# OpenTenkiEasyEda.net
KiCad netlist of a schematic drawn in EasyEDA Pro
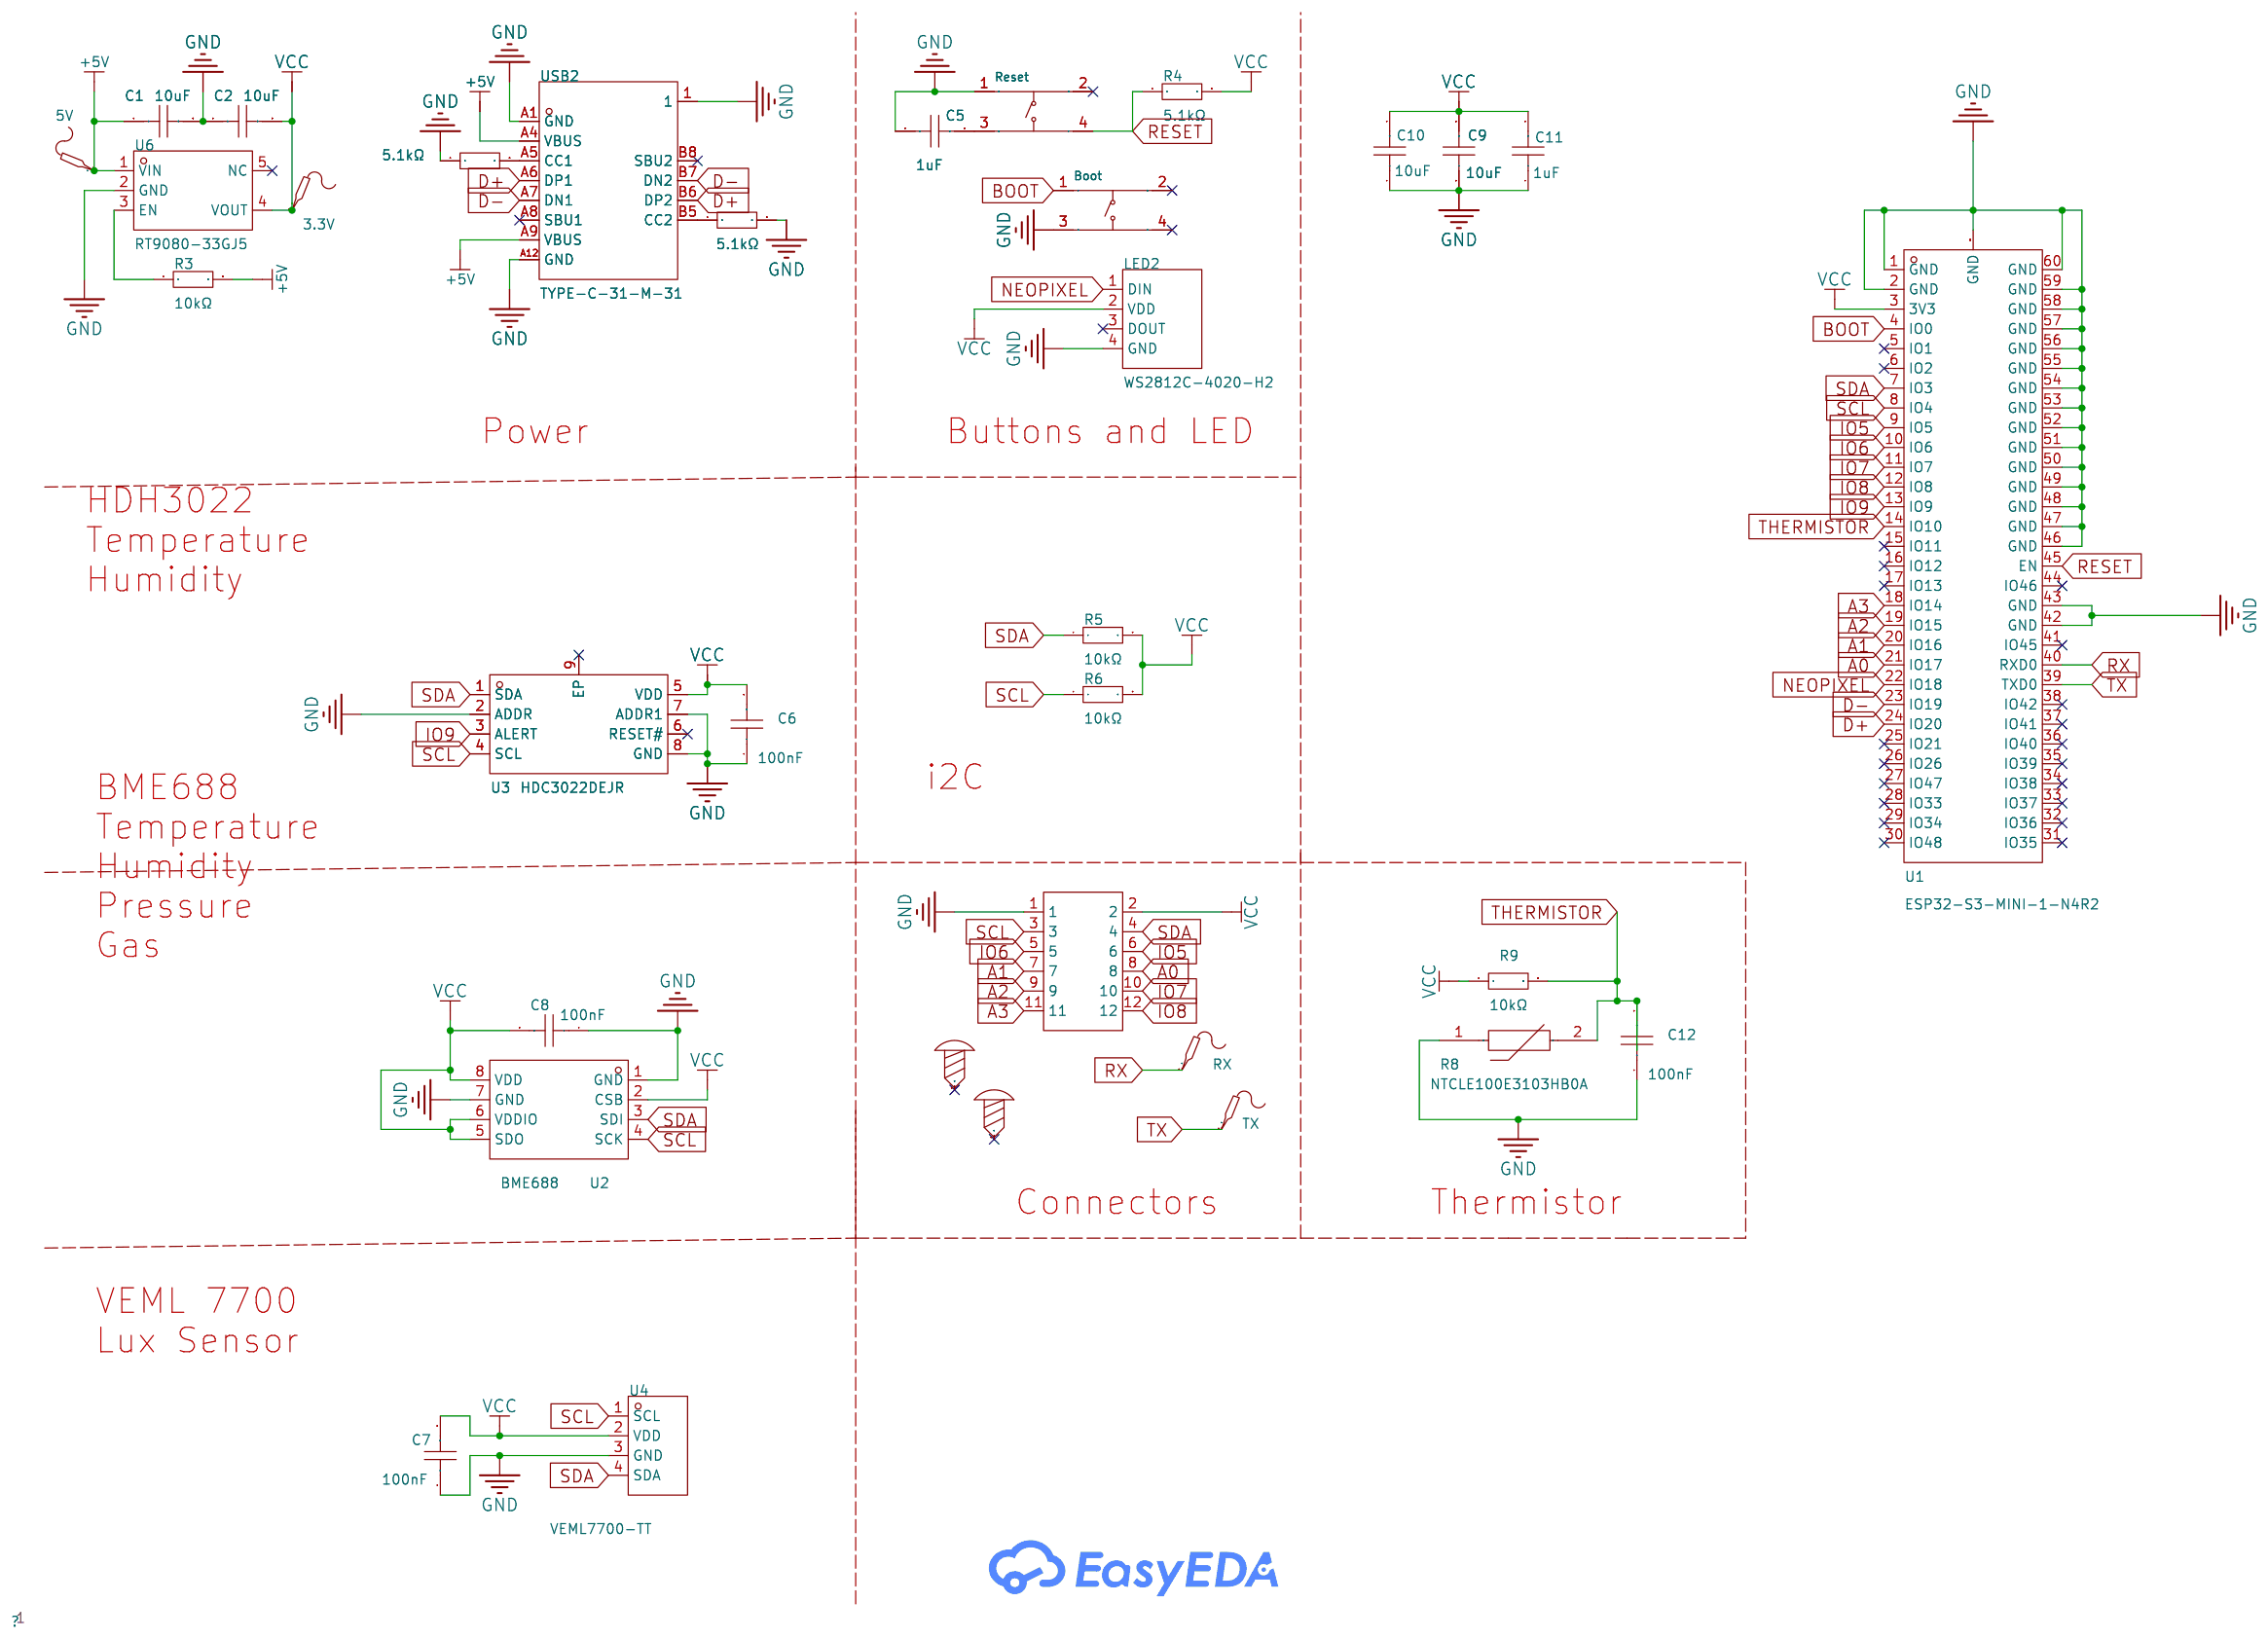
[diagram p0: schematic sheet]

(export (version "E")
  (design (tool "Eeschema 10.0.6"))
  (components
    (comp (ref "3.3V")
      (value "~")
      (footprint "easyedapro:Test-Point-0.5mm")
      (description "Test Point 测试点")
      (libsource (lib "easyedapro") (part "Test-Point"))
    )
    (comp (ref "5V")
      (value "~")
      (footprint "easyedapro:Test-Point-0.5mm")
      (description "Test Point 测试点")
      (libsource (lib "easyedapro") (part "Test-Point"))
    )
    (comp (ref "Boot")
      (value "TSD4A 250gf-DZ")
      (footprint "easyedapro:SW-SMD_TSD4A")
      (fields (field (name "Manufacturer") "SHOU HAN(首韩)"))
      (libsource (lib "easyedapro") (part "TSD4A 250GF-DZ"))
    )
    (comp (ref "C1")
      (value "10uF")
      (footprint "easyedapro:C0603")
      (fields
        (field (name "Manufacturer Part") "CL10A106KP8NNNC")
        (field (name "Manufacturer") "SAMSUNG(三星)")
      )
      (libsource (lib "easyedapro") (part "CL10A106KP8NNNC"))
    )
    (comp (ref "C2")
      (value "10uF")
      (footprint "easyedapro:C0603")
      (fields
        (field (name "Manufacturer Part") "CL10A106KP8NNNC")
        (field (name "Manufacturer") "SAMSUNG(三星)")
      )
      (libsource (lib "easyedapro") (part "CL10A106KP8NNNC"))
    )
    (comp (ref "C5")
      (value "1uF")
      (footprint "easyedapro:C0603")
      (fields
        (field (name "Manufacturer Part") "CL10A105KB8NNNC")
        (field (name "Manufacturer") "SAMSUNG(三星)")
      )
      (libsource (lib "easyedapro") (part "CL10A105KB8NNNC"))
    )
    (comp (ref "C6")
      (value "100nF")
      (footprint "easyedapro:C0603")
      (description "Capacitance:100nF Tolerance:±10% Tolerance:±10% Voltage Rating:50V Temperature Coefficient:X7R")
      (fields
        (field (name "Manufacturer Part") "CC0603KRX7R9BB104")
        (field (name "Manufacturer") "YAGEO(国巨)")
      )
      (libsource (lib "easyedapro") (part "CC0603KRX7R9BB104"))
    )
    (comp (ref "C7")
      (value "100nF")
      (footprint "easyedapro:C0603")
      (description "Capacitance:100nF Tolerance:±10% Tolerance:±10% Voltage Rating:50V Temperature Coefficient:X7R")
      (fields
        (field (name "Manufacturer Part") "CC0603KRX7R9BB104")
        (field (name "Manufacturer") "YAGEO(国巨)")
      )
      (libsource (lib "easyedapro") (part "CC0603KRX7R9BB104"))
    )
    (comp (ref "C8")
      (value "100nF")
      (footprint "easyedapro:C0603")
      (description "Capacitance:100nF Tolerance:±10% Tolerance:±10% Voltage Rating:50V Temperature Coefficient:X7R")
      (fields
        (field (name "Manufacturer Part") "CC0603KRX7R9BB104")
        (field (name "Manufacturer") "YAGEO(国巨)")
      )
      (libsource (lib "easyedapro") (part "CC0603KRX7R9BB104"))
    )
    (comp (ref "C9")
      (value "10uF")
      (footprint "easyedapro:C0603")
      (fields
        (field (name "Manufacturer Part") "CL10A106KP8NNNC")
        (field (name "Manufacturer") "SAMSUNG(三星)")
      )
      (libsource (lib "easyedapro") (part "CL10A106KP8NNNC"))
    )
    (comp (ref "C10")
      (value "10uF")
      (footprint "easyedapro:C0603")
      (fields
        (field (name "Manufacturer Part") "CL10A106KP8NNNC")
        (field (name "Manufacturer") "SAMSUNG(三星)")
      )
      (libsource (lib "easyedapro") (part "CL10A106KP8NNNC"))
    )
    (comp (ref "C11")
      (value "1uF")
      (footprint "easyedapro:C0603")
      (fields
        (field (name "Manufacturer Part") "CL10A105KB8NNNC")
        (field (name "Manufacturer") "SAMSUNG(三星)")
      )
      (libsource (lib "easyedapro") (part "CL10A105KB8NNNC"))
    )
    (comp (ref "C12")
      (value "100nF")
      (footprint "easyedapro:C0603")
      (description "Capacitance:100nF Tolerance:±10% Tolerance:±10% Voltage Rating:50V Temperature Coefficient:X7R")
      (fields
        (field (name "Manufacturer Part") "CC0603KRX7R9BB104")
        (field (name "Manufacturer") "YAGEO(国巨)")
      )
      (libsource (lib "easyedapro") (part "CC0603KRX7R9BB104"))
    )
    (comp (ref "LED2")
      (value "WS2812C-4020-H2")
      (footprint "easyedapro:LED-SMD_4P-L4.0-W1.7_DCS-CA4020A0R02G02B02CE004")
      (fields (field (name "Manufacturer") "worldsemi"))
      (libsource (lib "easyedapro") (part "WS2812C-4020-H2"))
    )
    (comp (ref "R3")
      (value "10kΩ")
      (footprint "easyedapro:R0603")
      (fields (field (name "Manufacturer Part") "RC0603FR-0710KL") (field (name "Manufacturer") "YAGEO(国巨)"))
      (libsource (lib "easyedapro") (part "RC0603FR-0710KL"))
    )
    (comp (ref "R4")
      (value "5.1kΩ")
      (footprint "easyedapro:R0603")
      (fields (field (name "Manufacturer Part") "RC0603FR-075K1L") (field (name "Manufacturer") "YAGEO(国巨)"))
      (libsource (lib "easyedapro") (part "RC0603FR-075K1L"))
    )
    (comp (ref "R5")
      (value "10kΩ")
      (footprint "easyedapro:R0603")
      (fields (field (name "Manufacturer Part") "RC0603FR-0710KL") (field (name "Manufacturer") "YAGEO(国巨)"))
      (libsource (lib "easyedapro") (part "RC0603FR-0710KL"))
    )
    (comp (ref "R6")
      (value "10kΩ")
      (footprint "easyedapro:R0603")
      (fields (field (name "Manufacturer Part") "RC0603FR-0710KL") (field (name "Manufacturer") "YAGEO(国巨)"))
      (libsource (lib "easyedapro") (part "RC0603FR-0710KL"))
    )
    (comp (ref "R8")
      (value "NTCLE100E3103HB0A")
      (footprint "easyedapro:RES-TH_L6.0-W3.0-P2.54-D0.6")
      (fields (field (name "Manufacturer") "VISHAY(威世)"))
      (libsource (lib "easyedapro") (part "NTCLE100E3103HT1"))
    )
    (comp (ref "R9")
      (value "10kΩ")
      (footprint "easyedapro:R0603")
      (fields (field (name "Manufacturer Part") "RC0603FR-0710KL") (field (name "Manufacturer") "YAGEO(国巨)"))
      (libsource (lib "easyedapro") (part "RC0603FR-0710KL"))
    )
    (comp (ref "R10")
      (value "5.1kΩ")
      (footprint "easyedapro:R0603")
      (fields (field (name "Manufacturer Part") "RC0603FR-075K1L") (field (name "Manufacturer") "YAGEO(国巨)"))
      (libsource (lib "easyedapro") (part "RC0603FR-075K1L"))
    )
    (comp (ref "R11")
      (value "5.1kΩ")
      (footprint "easyedapro:R0603")
      (fields (field (name "Manufacturer Part") "RC0603FR-075K1L") (field (name "Manufacturer") "YAGEO(国巨)"))
      (libsource (lib "easyedapro") (part "RC0603FR-075K1L"))
    )
    (comp (ref "Reset")
      (value "TSD4A 250gf-DZ")
      (footprint "easyedapro:SW-SMD_TSD4A")
      (fields (field (name "Manufacturer") "SHOU HAN(首韩)"))
      (libsource (lib "easyedapro") (part "TSD4A 250GF-DZ"))
    )
    (comp (ref "RX")
      (value "~")
      (footprint "easyedapro:Test-Point-0.5mm")
      (description "Test Point 测试点")
      (libsource (lib "easyedapro") (part "Test-Point"))
    )
    (comp (ref "SCREW2")
      (value "~")
      (footprint "easyedapro:Screw-Hole-M2")
      (libsource (lib "easyedapro") (part "Screw-Hole"))
    )
    (comp (ref "SCREW4")
      (value "~")
      (footprint "easyedapro:Screw-Hole-M2")
      (libsource (lib "easyedapro") (part "Screw-Hole"))
    )
    (comp (ref "TX")
      (value "~")
      (footprint "easyedapro:Test-Point-0.5mm")
      (description "Test Point 测试点")
      (libsource (lib "easyedapro") (part "Test-Point"))
    )
    (comp (ref "U1")
      (value "ESP32-S3-MINI-1-N4R2")
      (footprint "easyedapro:BULETM-SMD_ESP32-S3-MINI-1-N8")
      (description "Antenna Type:On-Board PCB Antenna")
      (fields (field (name "Manufacturer") "ESPRESSIF(乐鑫)"))
      (libsource (lib "easyedapro") (part "ESP32-S3-MINI-1-N4R2"))
    )
    (comp (ref "U2")
      (value "BME688")
      (footprint "easyedapro:LGA-8_L3.0-W3.0-P0.80_BME688")
      (fields (field (name "Manufacturer") "Bosch(博世)"))
      (libsource (lib "easyedapro") (part "BME688_C3664478"))
    )
    (comp (ref "U3")
      (value "HDC3022DEJR")
      (footprint "easyedapro:TDFN-8_L2.5-W2.5-P0.50-BL-EP")
      (description "Supply Voltage:1.62V~5.5V Supply Voltage:1.62V~5.5V")
      (fields (field (name "Manufacturer") "TI(德州仪器)"))
      (libsource (lib "easyedapro") (part "HDC3022DEJR"))
    )
    (comp (ref "U4")
      (value "VEML7700-TT")
      (footprint "easyedapro:SENSOR-SMD_EML7700-TT")
      (fields (field (name "Manufacturer") "VISHAY(威世)"))
      (libsource (lib "easyedapro") (part "VEML7700-TT"))
    )
    (comp (ref "U6")
      (value "RT9080-33GJ5")
      (footprint "easyedapro:SOT-23-5_L3.0-W1.5-P0.95-LS2.8-BL")
      (fields (field (name "Manufacturer") "TECH PUBLIC(台舟)"))
      (libsource (lib "easyedapro") (part "RT9080-33GJ5_C20617299"))
    )
    (comp (ref "U10")
      (value "ZX-PZ2.54-2-6PZZ")
      (footprint "easyedapro:HDR-TH_12P-P2.54-V-M-R2-C6-S2.54")
      (fields (field (name "Manufacturer") "Megastar(兆星)"))
      (libsource (lib "easyedapro") (part "ZX-PZ2.54-2-6PZZ"))
    )
    (comp (ref "USB2")
      (value "TYPE-C-31-M-31")
      (footprint "easyedapro:USB-C-SMD_TYPE-C-31-M-31")
      (fields (field (name "Manufacturer") "韩国韩荣"))
      (libsource (lib "easyedapro") (part "TYPE-C-31-M-31"))
    )
  )
  (nets
    (net (code "1") (name "+5V") (class "Default")
      (node (ref "5V") (pin "1") (pinfunction "1_1") (pintype "unspecified"))
      (node (ref "C1") (pin "1") (pinfunction "1_1") (pintype "unspecified"))
      (node (ref "R3") (pin "2") (pinfunction "2_2") (pintype "input"))
      (node (ref "U6") (pin "1") (pinfunction "VIN_1") (pintype "unspecified"))
      (node (ref "USB2") (pin "A4") (pinfunction "VBUS_A4") (pintype "unspecified"))
      (node (ref "USB2") (pin "A9") (pinfunction "VBUS_A9") (pintype "unspecified"))
    )
    (net (code "2") (name "A0") (class "Default")
      (node (ref "U1") (pin "21") (pinfunction "IO17_21") (pintype "unspecified"))
      (node (ref "U10") (pin "8") (pinfunction "8_8") (pintype "unspecified"))
    )
    (net (code "3") (name "A1") (class "Default")
      (node (ref "U1") (pin "20") (pinfunction "IO16_20") (pintype "unspecified"))
      (node (ref "U10") (pin "7") (pinfunction "7_7") (pintype "unspecified"))
    )
    (net (code "4") (name "A2") (class "Default")
      (node (ref "U1") (pin "19") (pinfunction "IO15_19") (pintype "unspecified"))
      (node (ref "U10") (pin "9") (pinfunction "9_9") (pintype "unspecified"))
    )
    (net (code "5") (name "A3") (class "Default")
      (node (ref "U1") (pin "18") (pinfunction "IO14_18") (pintype "unspecified"))
      (node (ref "U10") (pin "11") (pinfunction "11_11") (pintype "unspecified"))
    )
    (net (code "6") (name "BOOT") (class "Default")
      (node (ref "Boot") (pin "1") (pinfunction "1_1") (pintype "input"))
      (node (ref "U1") (pin "4") (pinfunction "IO0_4") (pintype "unspecified"))
    )
    (net (code "7") (name "D+") (class "Default")
      (node (ref "U1") (pin "24") (pinfunction "IO20_24") (pintype "unspecified"))
      (node (ref "USB2") (pin "A6") (pinfunction "DP1_A6") (pintype "unspecified"))
      (node (ref "USB2") (pin "B6") (pinfunction "DP2_B6") (pintype "unspecified"))
    )
    (net (code "8") (name "D-") (class "Default")
      (node (ref "U1") (pin "23") (pinfunction "IO19_23") (pintype "unspecified"))
      (node (ref "USB2") (pin "A7") (pinfunction "DN1_A7") (pintype "unspecified"))
      (node (ref "USB2") (pin "B7") (pinfunction "DN2_B7") (pintype "unspecified"))
    )
    (net (code "9") (name "GND") (class "Default")
      (node (ref "Boot") (pin "3") (pinfunction "3_3") (pintype "input"))
      (node (ref "C1") (pin "2") (pinfunction "2_2") (pintype "unspecified"))
      (node (ref "C10") (pin "1") (pinfunction "1_1") (pintype "unspecified"))
      (node (ref "C11") (pin "1") (pinfunction "1_1") (pintype "unspecified"))
      (node (ref "C12") (pin "1") (pinfunction "1_1") (pintype "unspecified"))
      (node (ref "C2") (pin "1") (pinfunction "1_1") (pintype "unspecified"))
      (node (ref "C5") (pin "1") (pinfunction "1_1") (pintype "unspecified"))
      (node (ref "C6") (pin "1") (pinfunction "1_1") (pintype "unspecified"))
      (node (ref "C7") (pin "1") (pinfunction "1_1") (pintype "unspecified"))
      (node (ref "C8") (pin "1") (pinfunction "1_1") (pintype "unspecified"))
      (node (ref "C9") (pin "1") (pinfunction "1_1") (pintype "unspecified"))
      (node (ref "LED2") (pin "4") (pinfunction "GND_4") (pintype "unspecified"))
      (node (ref "R10") (pin "2") (pinfunction "2_2") (pintype "input"))
      (node (ref "R11") (pin "1") (pinfunction "1_1") (pintype "input"))
      (node (ref "R8") (pin "1") (pinfunction "1_1") (pintype "input"))
      (node (ref "Reset") (pin "1") (pinfunction "1_1") (pintype "input"))
      (node (ref "U1") (pin "1") (pinfunction "GND_1") (pintype "unspecified"))
      (node (ref "U1") (pin "2") (pinfunction "GND_2") (pintype "unspecified"))
      (node (ref "U1") (pin "42") (pinfunction "GND_42") (pintype "unspecified"))
      (node (ref "U1") (pin "43") (pinfunction "GND_43") (pintype "unspecified"))
      (node (ref "U1") (pin "46") (pinfunction "GND_46") (pintype "unspecified"))
      (node (ref "U1") (pin "47") (pinfunction "GND_47") (pintype "unspecified"))
      (node (ref "U1") (pin "48") (pinfunction "GND_48") (pintype "unspecified"))
      (node (ref "U1") (pin "49") (pinfunction "GND_49") (pintype "unspecified"))
      (node (ref "U1") (pin "50") (pinfunction "GND_50") (pintype "unspecified"))
      (node (ref "U1") (pin "51") (pinfunction "GND_51") (pintype "unspecified"))
      (node (ref "U1") (pin "52") (pinfunction "GND_52") (pintype "unspecified"))
      (node (ref "U1") (pin "53") (pinfunction "GND_53") (pintype "unspecified"))
      (node (ref "U1") (pin "54") (pinfunction "GND_54") (pintype "unspecified"))
      (node (ref "U1") (pin "55") (pinfunction "GND_55") (pintype "unspecified"))
      (node (ref "U1") (pin "56") (pinfunction "GND_56") (pintype "unspecified"))
      (node (ref "U1") (pin "57") (pinfunction "GND_57") (pintype "unspecified"))
      (node (ref "U1") (pin "58") (pinfunction "GND_58") (pintype "unspecified"))
      (node (ref "U1") (pin "59") (pinfunction "GND_59") (pintype "unspecified"))
      (node (ref "U1") (pin "60") (pinfunction "GND_60") (pintype "unspecified"))
      (node (ref "U1") (pin "GND") (pinfunction "GND_GND") (pintype "unspecified"))
      (node (ref "U10") (pin "1") (pinfunction "1_1") (pintype "unspecified"))
      (node (ref "U2") (pin "1") (pinfunction "GND_1") (pintype "unspecified"))
      (node (ref "U2") (pin "7") (pinfunction "GND_7") (pintype "unspecified"))
      (node (ref "U3") (pin "2") (pinfunction "ADDR_2") (pintype "unspecified"))
      (node (ref "U3") (pin "7") (pinfunction "ADDR1_7") (pintype "unspecified"))
      (node (ref "U3") (pin "8") (pinfunction "GND_8") (pintype "unspecified"))
      (node (ref "U4") (pin "3") (pinfunction "GND_3") (pintype "unspecified"))
      (node (ref "U6") (pin "2") (pinfunction "GND_2") (pintype "unspecified"))
      (node (ref "USB2") (pin "1") (pinfunction "1_1") (pintype "unspecified"))
      (node (ref "USB2") (pin "A1") (pinfunction "GND_A1") (pintype "unspecified"))
      (node (ref "USB2") (pin "A12") (pinfunction "GND_A12") (pintype "unspecified"))
    )
    (net (code "10") (name "IO5") (class "Default")
      (node (ref "U1") (pin "9") (pinfunction "IO5_9") (pintype "unspecified"))
      (node (ref "U10") (pin "6") (pinfunction "6_6") (pintype "unspecified"))
    )
    (net (code "11") (name "IO6") (class "Default")
      (node (ref "U1") (pin "10") (pinfunction "IO6_10") (pintype "unspecified"))
      (node (ref "U10") (pin "5") (pinfunction "5_5") (pintype "unspecified"))
    )
    (net (code "12") (name "IO7") (class "Default")
      (node (ref "U1") (pin "11") (pinfunction "IO7_11") (pintype "unspecified"))
      (node (ref "U10") (pin "10") (pinfunction "10_10") (pintype "unspecified"))
    )
    (net (code "13") (name "IO8") (class "Default")
      (node (ref "U1") (pin "12") (pinfunction "IO8_12") (pintype "unspecified"))
      (node (ref "U10") (pin "12") (pinfunction "12_12") (pintype "unspecified"))
    )
    (net (code "14") (name "IO9") (class "Default")
      (node (ref "U1") (pin "13") (pinfunction "IO9_13") (pintype "unspecified"))
      (node (ref "U3") (pin "3") (pinfunction "ALERT_3") (pintype "unspecified"))
    )
    (net (code "15") (name "NEOPIXEL") (class "Default")
      (node (ref "LED2") (pin "1") (pinfunction "DIN_1") (pintype "unspecified"))
      (node (ref "U1") (pin "22") (pinfunction "IO18_22") (pintype "unspecified"))
    )
    (net (code "16") (name "Net-(C5-Pad2)") (class "Default")
      (node (ref "C5") (pin "2") (pinfunction "2_2") (pintype "unspecified"))
      (node (ref "Reset") (pin "3") (pinfunction "3_3") (pintype "input"))
    )
    (net (code "17") (name "Net-(U6-EN)") (class "Default")
      (node (ref "R3") (pin "1") (pinfunction "1_1") (pintype "input"))
      (node (ref "U6") (pin "3") (pinfunction "EN_3") (pintype "unspecified"))
    )
    (net (code "18") (name "Net-(USB2-CC1)") (class "Default")
      (node (ref "R11") (pin "2") (pinfunction "2_2") (pintype "input"))
      (node (ref "USB2") (pin "A5") (pinfunction "CC1_A5") (pintype "unspecified"))
    )
    (net (code "19") (name "Net-(USB2-CC2)") (class "Default")
      (node (ref "R10") (pin "1") (pinfunction "1_1") (pintype "input"))
      (node (ref "USB2") (pin "B5") (pinfunction "CC2_B5") (pintype "unspecified"))
    )
    (net (code "20") (name "RESET") (class "Default")
      (node (ref "R4") (pin "1") (pinfunction "1_1") (pintype "input"))
      (node (ref "Reset") (pin "4") (pinfunction "4_4") (pintype "input"))
      (node (ref "U1") (pin "45") (pinfunction "EN_45") (pintype "unspecified"))
    )
    (net (code "21") (name "RX") (class "Default")
      (node (ref "RX") (pin "1") (pinfunction "1_1") (pintype "unspecified"))
      (node (ref "U1") (pin "40") (pinfunction "RXD0_40") (pintype "unspecified"))
    )
    (net (code "22") (name "SCL") (class "Default")
      (node (ref "R6") (pin "1") (pinfunction "1_1") (pintype "input"))
      (node (ref "U1") (pin "8") (pinfunction "IO4_8") (pintype "unspecified"))
      (node (ref "U10") (pin "3") (pinfunction "3_3") (pintype "unspecified"))
      (node (ref "U2") (pin "4") (pinfunction "SCK_4") (pintype "unspecified"))
      (node (ref "U3") (pin "4") (pinfunction "SCL_4") (pintype "unspecified"))
      (node (ref "U4") (pin "1") (pinfunction "SCL_1") (pintype "unspecified"))
    )
    (net (code "23") (name "SDA") (class "Default")
      (node (ref "R5") (pin "1") (pinfunction "1_1") (pintype "input"))
      (node (ref "U1") (pin "7") (pinfunction "IO3_7") (pintype "unspecified"))
      (node (ref "U10") (pin "4") (pinfunction "4_4") (pintype "unspecified"))
      (node (ref "U2") (pin "3") (pinfunction "SDI_3") (pintype "unspecified"))
      (node (ref "U3") (pin "1") (pinfunction "SDA_1") (pintype "unspecified"))
      (node (ref "U4") (pin "4") (pinfunction "SDA_4") (pintype "unspecified"))
    )
    (net (code "24") (name "THERMISTOR") (class "Default")
      (node (ref "C12") (pin "2") (pinfunction "2_2") (pintype "unspecified"))
      (node (ref "R8") (pin "2") (pinfunction "2_2") (pintype "input"))
      (node (ref "R9") (pin "2") (pinfunction "2_2") (pintype "input"))
      (node (ref "U1") (pin "14") (pinfunction "IO10_14") (pintype "unspecified"))
    )
    (net (code "25") (name "TX") (class "Default")
      (node (ref "TX") (pin "1") (pinfunction "1_1") (pintype "unspecified"))
      (node (ref "U1") (pin "39") (pinfunction "TXD0_39") (pintype "unspecified"))
    )
    (net (code "26") (name "VCC") (class "Default")
      (node (ref "3.3V") (pin "1") (pinfunction "1_1") (pintype "unspecified"))
      (node (ref "C10") (pin "2") (pinfunction "2_2") (pintype "unspecified"))
      (node (ref "C11") (pin "2") (pinfunction "2_2") (pintype "unspecified"))
      (node (ref "C2") (pin "2") (pinfunction "2_2") (pintype "unspecified"))
      (node (ref "C6") (pin "2") (pinfunction "2_2") (pintype "unspecified"))
      (node (ref "C7") (pin "2") (pinfunction "2_2") (pintype "unspecified"))
      (node (ref "C8") (pin "2") (pinfunction "2_2") (pintype "unspecified"))
      (node (ref "C9") (pin "2") (pinfunction "2_2") (pintype "unspecified"))
      (node (ref "LED2") (pin "2") (pinfunction "VDD_2") (pintype "unspecified"))
      (node (ref "R4") (pin "2") (pinfunction "2_2") (pintype "input"))
      (node (ref "R5") (pin "2") (pinfunction "2_2") (pintype "input"))
      (node (ref "R6") (pin "2") (pinfunction "2_2") (pintype "input"))
      (node (ref "R9") (pin "1") (pinfunction "1_1") (pintype "input"))
      (node (ref "U1") (pin "3") (pinfunction "3V3_3") (pintype "unspecified"))
      (node (ref "U10") (pin "2") (pinfunction "2_2") (pintype "unspecified"))
      (node (ref "U2") (pin "2") (pinfunction "CSB_2") (pintype "unspecified"))
      (node (ref "U2") (pin "5") (pinfunction "SDO_5") (pintype "unspecified"))
      (node (ref "U2") (pin "6") (pinfunction "VDDIO_6") (pintype "unspecified"))
      (node (ref "U2") (pin "8") (pinfunction "VDD_8") (pintype "unspecified"))
      (node (ref "U3") (pin "5") (pinfunction "VDD_5") (pintype "unspecified"))
      (node (ref "U4") (pin "2") (pinfunction "VDD_2") (pintype "unspecified"))
      (node (ref "U6") (pin "4") (pinfunction "VOUT_4") (pintype "unspecified"))
    )
    (net (code "27") (name "unconnected-(Boot-Pad2)") (class "Default")
      (node (ref "Boot") (pin "2") (pinfunction "2_2") (pintype "input+no_connect"))
    )
    (net (code "28") (name "unconnected-(Boot-Pad4)") (class "Default")
      (node (ref "Boot") (pin "4") (pinfunction "4_4") (pintype "input+no_connect"))
    )
    (net (code "29") (name "unconnected-(LED2-DOUT-Pad3)") (class "Default")
      (node (ref "LED2") (pin "3") (pinfunction "DOUT_3") (pintype "unspecified+no_connect"))
    )
    (net (code "30") (name "unconnected-(Reset-Pad2)") (class "Default")
      (node (ref "Reset") (pin "2") (pinfunction "2_2") (pintype "input+no_connect"))
    )
    (net (code "31") (name "unconnected-(SCREW2-Pad1)") (class "Default")
      (node (ref "SCREW2") (pin "1") (pinfunction "1_1") (pintype "input+no_connect"))
    )
    (net (code "32") (name "unconnected-(SCREW4-Pad1)") (class "Default")
      (node (ref "SCREW4") (pin "1") (pinfunction "1_1") (pintype "input+no_connect"))
    )
    (net (code "33") (name "unconnected-(U1-IO1-Pad5)") (class "Default")
      (node (ref "U1") (pin "5") (pinfunction "IO1_5") (pintype "unspecified+no_connect"))
    )
    (net (code "34") (name "unconnected-(U1-IO2-Pad6)") (class "Default")
      (node (ref "U1") (pin "6") (pinfunction "IO2_6") (pintype "unspecified+no_connect"))
    )
    (net (code "35") (name "unconnected-(U1-IO11-Pad15)") (class "Default")
      (node (ref "U1") (pin "15") (pinfunction "IO11_15") (pintype "unspecified+no_connect"))
    )
    (net (code "36") (name "unconnected-(U1-IO12-Pad16)") (class "Default")
      (node (ref "U1") (pin "16") (pinfunction "IO12_16") (pintype "unspecified+no_connect"))
    )
    (net (code "37") (name "unconnected-(U1-IO13-Pad17)") (class "Default")
      (node (ref "U1") (pin "17") (pinfunction "IO13_17") (pintype "unspecified+no_connect"))
    )
    (net (code "38") (name "unconnected-(U1-IO21-Pad25)") (class "Default")
      (node (ref "U1") (pin "25") (pinfunction "IO21_25") (pintype "unspecified+no_connect"))
    )
    (net (code "39") (name "unconnected-(U1-IO26-Pad26)") (class "Default")
      (node (ref "U1") (pin "26") (pinfunction "IO26_26") (pintype "unspecified+no_connect"))
    )
    (net (code "40") (name "unconnected-(U1-IO33-Pad28)") (class "Default")
      (node (ref "U1") (pin "28") (pinfunction "IO33_28") (pintype "unspecified+no_connect"))
    )
    (net (code "41") (name "unconnected-(U1-IO34-Pad29)") (class "Default")
      (node (ref "U1") (pin "29") (pinfunction "IO34_29") (pintype "unspecified+no_connect"))
    )
    (net (code "42") (name "unconnected-(U1-IO35-Pad31)") (class "Default")
      (node (ref "U1") (pin "31") (pinfunction "IO35_31") (pintype "unspecified+no_connect"))
    )
    (net (code "43") (name "unconnected-(U1-IO36-Pad32)") (class "Default")
      (node (ref "U1") (pin "32") (pinfunction "IO36_32") (pintype "unspecified+no_connect"))
    )
    (net (code "44") (name "unconnected-(U1-IO37-Pad33)") (class "Default")
      (node (ref "U1") (pin "33") (pinfunction "IO37_33") (pintype "unspecified+no_connect"))
    )
    (net (code "45") (name "unconnected-(U1-IO38-Pad34)") (class "Default")
      (node (ref "U1") (pin "34") (pinfunction "IO38_34") (pintype "unspecified+no_connect"))
    )
    (net (code "46") (name "unconnected-(U1-IO39-Pad35)") (class "Default")
      (node (ref "U1") (pin "35") (pinfunction "IO39_35") (pintype "unspecified+no_connect"))
    )
    (net (code "47") (name "unconnected-(U1-IO40-Pad36)") (class "Default")
      (node (ref "U1") (pin "36") (pinfunction "IO40_36") (pintype "unspecified+no_connect"))
    )
    (net (code "48") (name "unconnected-(U1-IO41-Pad37)") (class "Default")
      (node (ref "U1") (pin "37") (pinfunction "IO41_37") (pintype "unspecified+no_connect"))
    )
    (net (code "49") (name "unconnected-(U1-IO42-Pad38)") (class "Default")
      (node (ref "U1") (pin "38") (pinfunction "IO42_38") (pintype "unspecified+no_connect"))
    )
    (net (code "50") (name "unconnected-(U1-IO45-Pad41)") (class "Default")
      (node (ref "U1") (pin "41") (pinfunction "IO45_41") (pintype "unspecified+no_connect"))
    )
    (net (code "51") (name "unconnected-(U1-IO46-Pad44)") (class "Default")
      (node (ref "U1") (pin "44") (pinfunction "IO46_44") (pintype "unspecified+no_connect"))
    )
    (net (code "52") (name "unconnected-(U1-IO47-Pad27)") (class "Default")
      (node (ref "U1") (pin "27") (pinfunction "IO47_27") (pintype "unspecified+no_connect"))
    )
    (net (code "53") (name "unconnected-(U1-IO48-Pad30)") (class "Default")
      (node (ref "U1") (pin "30") (pinfunction "IO48_30") (pintype "unspecified+no_connect"))
    )
    (net (code "54") (name "unconnected-(U3-EP-Pad9)") (class "Default")
      (node (ref "U3") (pin "9") (pinfunction "EP_9") (pintype "unspecified+no_connect"))
    )
    (net (code "55") (name "unconnected-(U3-RESET#-Pad6)") (class "Default")
      (node (ref "U3") (pin "6") (pinfunction "RESET#_6") (pintype "unspecified+no_connect"))
    )
    (net (code "56") (name "unconnected-(U6-NC-Pad5)") (class "Default")
      (node (ref "U6") (pin "5") (pinfunction "NC_5") (pintype "unspecified+no_connect"))
    )
    (net (code "57") (name "unconnected-(USB2-SBU1-PadA8)") (class "Default")
      (node (ref "USB2") (pin "A8") (pinfunction "SBU1_A8") (pintype "unspecified+no_connect"))
    )
    (net (code "58") (name "unconnected-(USB2-SBU2-PadB8)") (class "Default")
      (node (ref "USB2") (pin "B8") (pinfunction "SBU2_B8") (pintype "unspecified+no_connect"))
    )
  )
)
